# UI_MAIN.net
KiCad netlist of a schematic drawn in Altium Designer
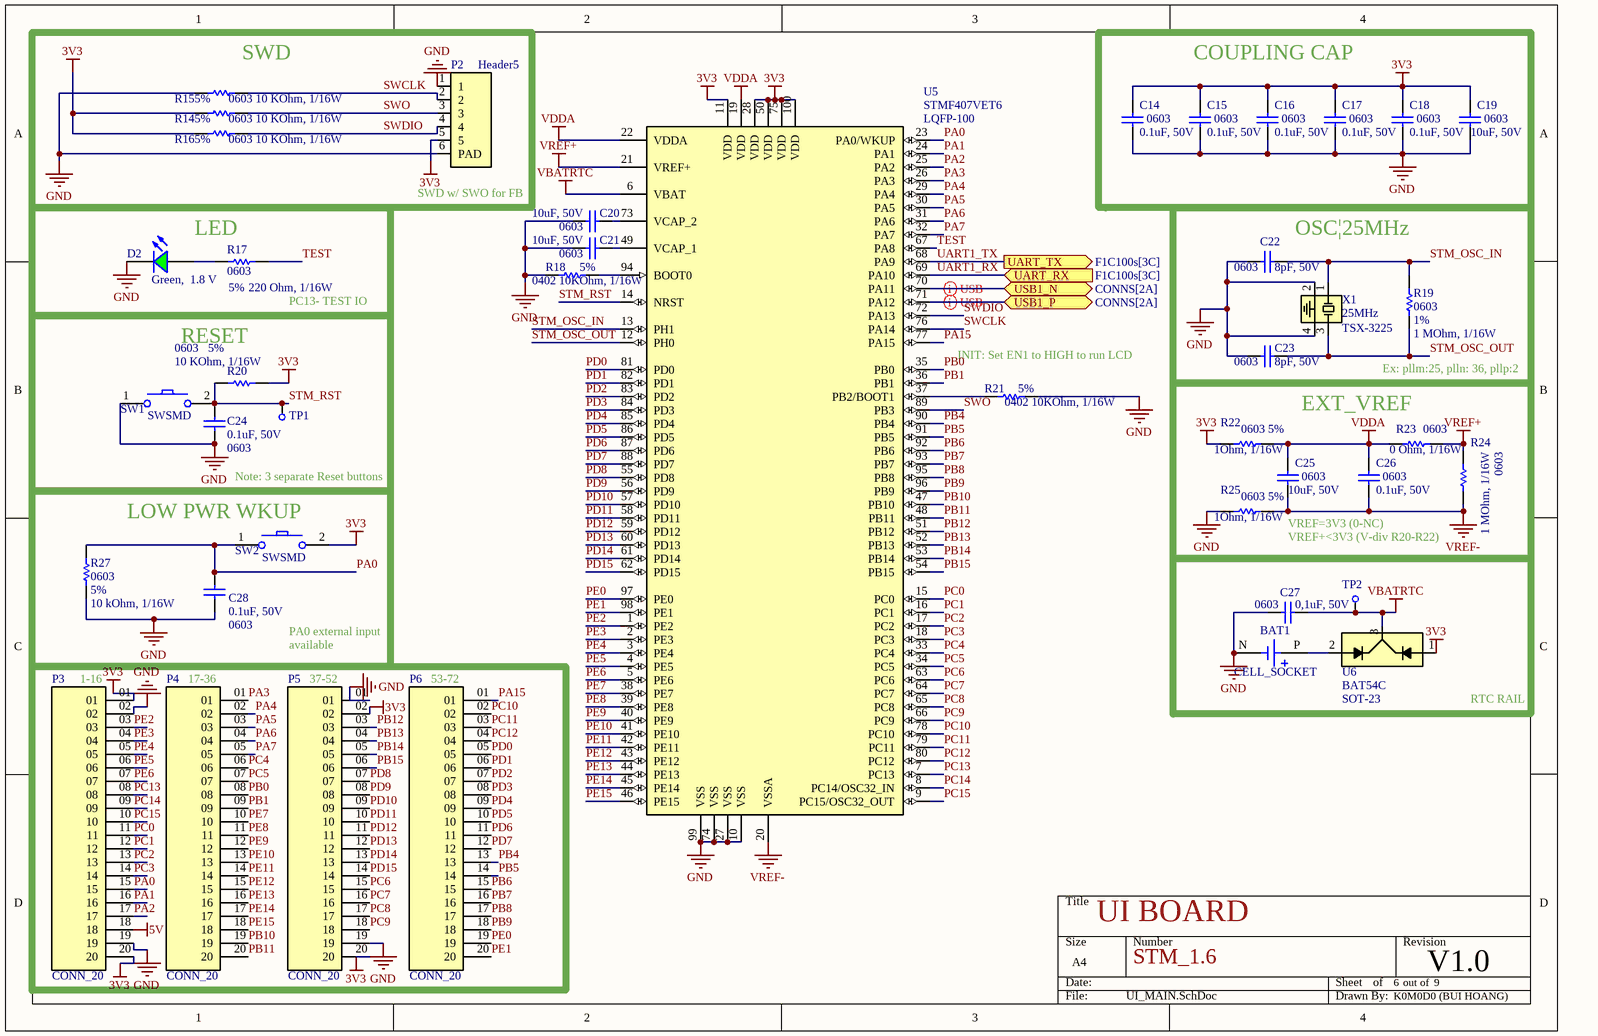
[diagram p0: UI_MAIN.SchDoc]

(export (version "E")
  (design (tool "Eeschema 10.0.6"))
  (components
    (comp (ref "BAT1")
      (value "CELL_SOCKET")
      (footprint "CELL_SOCKET")
      (description "Battery Holder (CELL_PIN)")
      (libsource (lib "DisplayLib") (part "CELL_SOCKET"))
    )
    (comp (ref "C14")
      (value "0.1uF, 50V")
      (footprint "C_0603")
      (description "CAP_0603")
      (fields (field (name "PACKAGE") "0603"))
      (libsource (lib "DisplayLib") (part "CAP_0603"))
    )
    (comp (ref "C15")
      (value "0.1uF, 50V")
      (footprint "C_0603")
      (description "CAP_0603")
      (fields (field (name "PACKAGE") "0603"))
      (libsource (lib "DisplayLib") (part "CAP_0603"))
    )
    (comp (ref "C16")
      (value "0.1uF, 50V")
      (footprint "C_0603")
      (description "CAP_0603")
      (fields (field (name "PACKAGE") "0603"))
      (libsource (lib "DisplayLib") (part "CAP_0603"))
    )
    (comp (ref "C17")
      (value "0.1uF, 50V")
      (footprint "C_0603")
      (description "CAP_0603")
      (fields (field (name "PACKAGE") "0603"))
      (libsource (lib "DisplayLib") (part "CAP_0603"))
    )
    (comp (ref "C18")
      (value "0.1uF, 50V")
      (footprint "C_0603")
      (description "CAP_0603")
      (fields (field (name "PACKAGE") "0603"))
      (libsource (lib "DisplayLib") (part "CAP_0603"))
    )
    (comp (ref "C19")
      (value "10uF, 50V")
      (footprint "C_0603")
      (description "CAP_0603")
      (fields (field (name "PACKAGE") "0603"))
      (libsource (lib "DisplayLib") (part "CAP_0603"))
    )
    (comp (ref "C20")
      (value "10uF, 50V")
      (footprint "C_0603")
      (description "CAP_0603")
      (fields (field (name "PACKAGE") "0603"))
      (libsource (lib "DisplayLib") (part "CAP_0603"))
    )
    (comp (ref "C21")
      (value "10uF, 50V")
      (footprint "C_0603")
      (description "CAP_0603")
      (fields (field (name "PACKAGE") "0603"))
      (libsource (lib "DisplayLib") (part "CAP_0603"))
    )
    (comp (ref "C22")
      (value "8pF, 50V")
      (footprint "C_0603")
      (description "CAP_0603")
      (fields (field (name "PACKAGE") "0603"))
      (libsource (lib "DisplayLib") (part "CAP_0603"))
    )
    (comp (ref "C23")
      (value "8pF, 50V")
      (footprint "C_0603")
      (description "CAP_0603")
      (fields (field (name "PACKAGE") "0603"))
      (libsource (lib "DisplayLib") (part "CAP_0603"))
    )
    (comp (ref "C24")
      (value "0.1uF, 50V")
      (footprint "C_0603")
      (description "CAP_0603")
      (fields (field (name "PACKAGE") "0603"))
      (libsource (lib "DisplayLib") (part "CAP_0603"))
    )
    (comp (ref "C25")
      (value "10uF, 50V")
      (footprint "C_0603")
      (description "CAP_0603")
      (fields (field (name "PACKAGE") "0603"))
      (libsource (lib "DisplayLib") (part "CAP_0603"))
    )
    (comp (ref "C26")
      (value "0.1uF, 50V")
      (footprint "C_0603")
      (description "CAP_0603")
      (fields (field (name "PACKAGE") "0603"))
      (libsource (lib "DisplayLib") (part "CAP_0603"))
    )
    (comp (ref "C27")
      (value "0,1uF, 50V")
      (footprint "C_0603")
      (description "CAP_0603")
      (fields (field (name "PACKAGE") "0603"))
      (libsource (lib "DisplayLib") (part "CAP_0603"))
    )
    (comp (ref "C28")
      (value "0.1uF, 50V")
      (footprint "C_0603")
      (description "CAP_0603")
      (fields (field (name "PACKAGE") "0603"))
      (libsource (lib "DisplayLib") (part "CAP_0603"))
    )
    (comp (ref "D2")
      (value "Green,  1.8 V")
      (footprint "LED_0603")
      (description "Green LED")
      (libsource (lib "DisplayLib") (part "GREEN"))
    )
    (comp (ref "P2")
      (value "Header5")
      (footprint "CONN_Header5")
      (description "Header 5 pins (2.54mm)")
      (libsource (lib "DisplayLib") (part "HEADER5"))
    )
    (comp (ref "P3")
      (value "CONN_20")
      (footprint "CONN_20")
      (description "Header 20 pins (2.54mm)")
      (libsource (lib "DisplayLib") (part "CONN_20"))
    )
    (comp (ref "P4")
      (value "CONN_20")
      (footprint "CONN_20")
      (description "Header 20 pins (2.54mm)")
      (libsource (lib "DisplayLib") (part "CONN_20"))
    )
    (comp (ref "P5")
      (value "CONN_20")
      (footprint "CONN_20")
      (description "Header 20 pins (2.54mm)")
      (libsource (lib "DisplayLib") (part "CONN_20"))
    )
    (comp (ref "P6")
      (value "CONN_20")
      (footprint "CONN_20")
      (description "Header 20 pins (2.54mm)")
      (libsource (lib "DisplayLib") (part "CONN_20"))
    )
    (comp (ref "R14")
      (value "10 KOhm, 1/16W")
      (footprint "R_0603")
      (description "RES_0603")
      (fields (field (name "PACKAGE") "0603") (field (name "ACC") "5%"))
      (libsource (lib "DisplayLib") (part "RES_0603"))
    )
    (comp (ref "R15")
      (value "10 KOhm, 1/16W")
      (footprint "R_0603")
      (description "RES_0603")
      (fields (field (name "PACKAGE") "0603") (field (name "ACC") "5%"))
      (libsource (lib "DisplayLib") (part "RES_0603"))
    )
    (comp (ref "R16")
      (value "10 KOhm, 1/16W")
      (footprint "R_0603")
      (description "RES_0603")
      (fields (field (name "PACKAGE") "0603") (field (name "ACC") "5%"))
      (libsource (lib "DisplayLib") (part "RES_0603"))
    )
    (comp (ref "R17")
      (value "220 Ohm, 1/16W")
      (footprint "R_0603")
      (description "RES_0603")
      (fields (field (name "PACKAGE") "0603") (field (name "ACC") "5%"))
      (libsource (lib "DisplayLib") (part "RES_0603"))
    )
    (comp (ref "R18")
      (value "10KOhm, 1/16W")
      (footprint "R_0402")
      (description "RES_0402")
      (fields (field (name "PACKAGE") "0402") (field (name "ACC") "5%"))
      (libsource (lib "DisplayLib") (part "RES_0402"))
    )
    (comp (ref "R19")
      (value "1 MOhm, 1/16W")
      (footprint "R_0603")
      (description "RES_0603")
      (fields (field (name "PACKAGE") "0603") (field (name "ACC") "1%"))
      (libsource (lib "DisplayLib") (part "RES_0603"))
    )
    (comp (ref "R20")
      (value "10 KOhm, 1/16W")
      (footprint "R_0603")
      (description "RES_0603")
      (fields (field (name "PACKAGE") "0603") (field (name "ACC") "5%"))
      (libsource (lib "DisplayLib") (part "RES_0603"))
    )
    (comp (ref "R21")
      (value "10KOhm, 1/16W")
      (footprint "R_0402")
      (description "RES_0402")
      (fields (field (name "PACKAGE") "0402") (field (name "ACC") "5%"))
      (libsource (lib "DisplayLib") (part "RES_0402"))
    )
    (comp (ref "R22")
      (value "1Ohm, 1/16W")
      (footprint "R_0603")
      (description "RES_0603")
      (fields (field (name "PACKAGE") "0603") (field (name "ACC") "5%"))
      (libsource (lib "DisplayLib") (part "RES_0603"))
    )
    (comp (ref "R23")
      (value "0 Ohm, 1/16W")
      (footprint "R_0603")
      (description "RES_0603")
      (fields (field (name "PACKAGE") "0603"))
      (libsource (lib "DisplayLib") (part "RES_0603"))
    )
    (comp (ref "R24")
      (value "1 MOhm, 1/16W")
      (footprint "R_0603")
      (description "RES_0603")
      (fields (field (name "PACKAGE") "0603"))
      (libsource (lib "DisplayLib") (part "RES_0603"))
    )
    (comp (ref "R25")
      (value "1Ohm, 1/16W")
      (footprint "R_0603")
      (description "RES_0603")
      (fields (field (name "PACKAGE") "0603") (field (name "ACC") "5%"))
      (libsource (lib "DisplayLib") (part "RES_0603"))
    )
    (comp (ref "R27")
      (value "10 kOhm, 1/16W")
      (footprint "R_0603")
      (description "RES_0603")
      (fields (field (name "PACKAGE") "0603") (field (name "ACC") "5%"))
      (libsource (lib "DisplayLib") (part "RES_0603"))
    )
    (comp (ref "SW1")
      (value "SWSMD")
      (footprint "SW_SMD_NOGND")
      (description "SW_SMD")
      (libsource (lib "DisplayLib") (part "SWSMD_NOGND"))
    )
    (comp (ref "SW2")
      (value "SWSMD")
      (footprint "SW_SMD_NOGND")
      (description "SW_SMD")
      (libsource (lib "DisplayLib") (part "SWSMD_NOGND"))
    )
    (comp (ref "TP1")
      (value "TESTPT")
      (footprint "TESTPT")
      (description "Test point")
      (libsource (lib "DisplayLib") (part "TESTPT"))
    )
    (comp (ref "TP2")
      (value "TESTPT")
      (footprint "TESTPT")
      (description "Test point")
      (libsource (lib "DisplayLib") (part "TESTPT"))
    )
    (comp (ref "U5")
      (value "STMF407VET6")
      (footprint "PKG_LQFP-100")
      (fields (field (name "PACKAGE") "LQFP-100"))
      (libsource (lib "DisplayLib") (part "STMF407VET6"))
    )
    (comp (ref "U6")
      (value "BAT54C")
      (footprint "PKG_SOT-23")
      (description "P-Channel 30 V 4A (Ta) 1.4W (Ta) Surface Mount SOT-23-3")
      (fields (field (name "PACKAGE") "SOT-23"))
      (libsource (lib "DisplayLib") (part "BAT54C"))
    )
    (comp (ref "X1")
      (value "25MHz")
      (footprint "PKG_TSX-3225")
      (description "Crystal, 25 MHz, -30 to 85 degC, 3.2 x 2.5 x 0.9 mm SMD")
      (fields (field (name "PACKAGE") "TSX-3225"))
      (libsource (lib "DisplayLib") (part "XTAL"))
    )
  )
  (nets
    (net (code "1") (name "/PA0") (class "Default")
      (node (ref "C28") (pin "2") (pinfunction "2_2") (pintype "passive"))
      (node (ref "P3") (pin "15") (pinfunction "15_15") (pintype "passive"))
      (node (ref "R27") (pin "2") (pinfunction "2_2") (pintype "passive"))
      (node (ref "SW2") (pin "1") (pinfunction "1_1") (pintype "passive"))
      (node (ref "U5") (pin "23") (pinfunction "PA0/WKUP_23") (pintype "bidirectional"))
    )
    (net (code "2") (name "/PA1") (class "Default")
      (node (ref "P3") (pin "16") (pinfunction "16_16") (pintype "passive"))
      (node (ref "U5") (pin "24") (pinfunction "PA1_24") (pintype "bidirectional"))
    )
    (net (code "3") (name "/PA2") (class "Default")
      (node (ref "P3") (pin "17") (pinfunction "17_17") (pintype "passive"))
      (node (ref "U5") (pin "25") (pinfunction "PA2_25") (pintype "bidirectional"))
    )
    (net (code "4") (name "/PA3") (class "Default")
      (node (ref "P4") (pin "01") (pinfunction "01_01") (pintype "passive"))
      (node (ref "U5") (pin "26") (pinfunction "PA3_26") (pintype "bidirectional"))
    )
    (net (code "5") (name "/PA4") (class "Default")
      (node (ref "P4") (pin "02") (pinfunction "02_02") (pintype "passive"))
      (node (ref "U5") (pin "29") (pinfunction "PA4_29") (pintype "bidirectional"))
    )
    (net (code "6") (name "/PA5") (class "Default")
      (node (ref "P4") (pin "03") (pinfunction "03_03") (pintype "passive"))
      (node (ref "U5") (pin "30") (pinfunction "PA5_30") (pintype "bidirectional"))
    )
    (net (code "7") (name "/PA6") (class "Default")
      (node (ref "P4") (pin "04") (pinfunction "04_04") (pintype "passive"))
      (node (ref "U5") (pin "31") (pinfunction "PA6_31") (pintype "bidirectional"))
    )
    (net (code "8") (name "/PA7") (class "Default")
      (node (ref "P4") (pin "05") (pinfunction "05_05") (pintype "passive"))
      (node (ref "U5") (pin "32") (pinfunction "PA7_32") (pintype "bidirectional"))
    )
    (net (code "9") (name "/PA15") (class "Default")
      (node (ref "P6") (pin "01") (pinfunction "01_01") (pintype "passive"))
      (node (ref "U5") (pin "77") (pinfunction "PA15_77") (pintype "bidirectional"))
    )
    (net (code "10") (name "/PB0") (class "Default")
      (node (ref "P4") (pin "08") (pinfunction "08_08") (pintype "passive"))
      (node (ref "U5") (pin "35") (pinfunction "PB0_35") (pintype "bidirectional"))
    )
    (net (code "11") (name "/PB1") (class "Default")
      (node (ref "P4") (pin "09") (pinfunction "09_09") (pintype "passive"))
      (node (ref "U5") (pin "36") (pinfunction "PB1_36") (pintype "bidirectional"))
    )
    (net (code "12") (name "/PB4") (class "Default")
      (node (ref "P6") (pin "13") (pinfunction "13_13") (pintype "passive"))
      (node (ref "U5") (pin "90") (pinfunction "PB4_90") (pintype "bidirectional"))
    )
    (net (code "13") (name "/PB5") (class "Default")
      (node (ref "P6") (pin "14") (pinfunction "14_14") (pintype "passive"))
      (node (ref "U5") (pin "91") (pinfunction "PB5_91") (pintype "bidirectional"))
    )
    (net (code "14") (name "/PB6") (class "Default")
      (node (ref "P6") (pin "15") (pinfunction "15_15") (pintype "passive"))
      (node (ref "U5") (pin "92") (pinfunction "PB6_92") (pintype "bidirectional"))
    )
    (net (code "15") (name "/PB7") (class "Default")
      (node (ref "P6") (pin "16") (pinfunction "16_16") (pintype "passive"))
      (node (ref "U5") (pin "93") (pinfunction "PB7_93") (pintype "bidirectional"))
    )
    (net (code "16") (name "/PB8") (class "Default")
      (node (ref "P6") (pin "17") (pinfunction "17_17") (pintype "passive"))
      (node (ref "U5") (pin "95") (pinfunction "PB8_95") (pintype "bidirectional"))
    )
    (net (code "17") (name "/PB9") (class "Default")
      (node (ref "P6") (pin "18") (pinfunction "18_18") (pintype "passive"))
      (node (ref "U5") (pin "96") (pinfunction "PB9_96") (pintype "bidirectional"))
    )
    (net (code "18") (name "/PB10") (class "Default")
      (node (ref "P4") (pin "19") (pinfunction "19_19") (pintype "passive"))
      (node (ref "U5") (pin "47") (pinfunction "PB10_47") (pintype "bidirectional"))
    )
    (net (code "19") (name "/PB11") (class "Default")
      (node (ref "P4") (pin "20") (pinfunction "20_20") (pintype "passive"))
      (node (ref "U5") (pin "48") (pinfunction "PB11_48") (pintype "bidirectional"))
    )
    (net (code "20") (name "/PB12") (class "Default")
      (node (ref "P5") (pin "03") (pinfunction "03_03") (pintype "passive"))
      (node (ref "U5") (pin "51") (pinfunction "PB12_51") (pintype "bidirectional"))
    )
    (net (code "21") (name "/PB13") (class "Default")
      (node (ref "P5") (pin "04") (pinfunction "04_04") (pintype "passive"))
      (node (ref "U5") (pin "52") (pinfunction "PB13_52") (pintype "bidirectional"))
    )
    (net (code "22") (name "/PB14") (class "Default")
      (node (ref "P5") (pin "05") (pinfunction "05_05") (pintype "passive"))
      (node (ref "U5") (pin "53") (pinfunction "PB14_53") (pintype "bidirectional"))
    )
    (net (code "23") (name "/PB15") (class "Default")
      (node (ref "P5") (pin "06") (pinfunction "06_06") (pintype "passive"))
      (node (ref "U5") (pin "54") (pinfunction "PB15_54") (pintype "bidirectional"))
    )
    (net (code "24") (name "/PC0") (class "Default")
      (node (ref "P3") (pin "11") (pinfunction "11_11") (pintype "passive"))
      (node (ref "U5") (pin "15") (pinfunction "PC0_15") (pintype "bidirectional"))
    )
    (net (code "25") (name "/PC1") (class "Default")
      (node (ref "P3") (pin "12") (pinfunction "12_12") (pintype "passive"))
      (node (ref "U5") (pin "16") (pinfunction "PC1_16") (pintype "bidirectional"))
    )
    (net (code "26") (name "/PC2") (class "Default")
      (node (ref "P3") (pin "13") (pinfunction "13_13") (pintype "passive"))
      (node (ref "U5") (pin "17") (pinfunction "PC2_17") (pintype "bidirectional"))
    )
    (net (code "27") (name "/PC3") (class "Default")
      (node (ref "P3") (pin "14") (pinfunction "14_14") (pintype "passive"))
      (node (ref "U5") (pin "18") (pinfunction "PC3_18") (pintype "bidirectional"))
    )
    (net (code "28") (name "/PC4") (class "Default")
      (node (ref "P4") (pin "06") (pinfunction "06_06") (pintype "passive"))
      (node (ref "U5") (pin "33") (pinfunction "PC4_33") (pintype "bidirectional"))
    )
    (net (code "29") (name "/PC5") (class "Default")
      (node (ref "P4") (pin "07") (pinfunction "07_07") (pintype "passive"))
      (node (ref "U5") (pin "34") (pinfunction "PC5_34") (pintype "bidirectional"))
    )
    (net (code "30") (name "/PC6") (class "Default")
      (node (ref "P5") (pin "15") (pinfunction "15_15") (pintype "passive"))
      (node (ref "U5") (pin "63") (pinfunction "PC6_63") (pintype "bidirectional"))
    )
    (net (code "31") (name "/PC7") (class "Default")
      (node (ref "P5") (pin "16") (pinfunction "16_16") (pintype "passive"))
      (node (ref "U5") (pin "64") (pinfunction "PC7_64") (pintype "bidirectional"))
    )
    (net (code "32") (name "/PC8") (class "Default")
      (node (ref "P5") (pin "17") (pinfunction "17_17") (pintype "passive"))
      (node (ref "U5") (pin "65") (pinfunction "PC8_65") (pintype "bidirectional"))
    )
    (net (code "33") (name "/PC9") (class "Default")
      (node (ref "P5") (pin "18") (pinfunction "18_18") (pintype "passive"))
      (node (ref "U5") (pin "66") (pinfunction "PC9_66") (pintype "bidirectional"))
    )
    (net (code "34") (name "/PC10") (class "Default")
      (node (ref "P6") (pin "02") (pinfunction "02_02") (pintype "passive"))
      (node (ref "U5") (pin "78") (pinfunction "PC10_78") (pintype "bidirectional"))
    )
    (net (code "35") (name "/PC11") (class "Default")
      (node (ref "P6") (pin "03") (pinfunction "03_03") (pintype "passive"))
      (node (ref "U5") (pin "79") (pinfunction "PC11_79") (pintype "bidirectional"))
    )
    (net (code "36") (name "/PC12") (class "Default")
      (node (ref "P6") (pin "04") (pinfunction "04_04") (pintype "passive"))
      (node (ref "U5") (pin "80") (pinfunction "PC12_80") (pintype "bidirectional"))
    )
    (net (code "37") (name "/PC13") (class "Default")
      (node (ref "P3") (pin "08") (pinfunction "08_08") (pintype "passive"))
      (node (ref "U5") (pin "7") (pinfunction "PC13_7") (pintype "bidirectional"))
    )
    (net (code "38") (name "/PC14") (class "Default")
      (node (ref "P3") (pin "09") (pinfunction "09_09") (pintype "passive"))
      (node (ref "U5") (pin "8") (pinfunction "PC14/OSC32_IN_8") (pintype "bidirectional"))
    )
    (net (code "39") (name "/PC15") (class "Default")
      (node (ref "P3") (pin "10") (pinfunction "10_10") (pintype "passive"))
      (node (ref "U5") (pin "9") (pinfunction "PC15/OSC32_OUT_9") (pintype "bidirectional"))
    )
    (net (code "40") (name "/PD0") (class "Default")
      (node (ref "P6") (pin "05") (pinfunction "05_05") (pintype "passive"))
      (node (ref "U5") (pin "81") (pinfunction "PD0_81") (pintype "bidirectional"))
    )
    (net (code "41") (name "/PD1") (class "Default")
      (node (ref "P6") (pin "06") (pinfunction "06_06") (pintype "passive"))
      (node (ref "U5") (pin "82") (pinfunction "PD1_82") (pintype "bidirectional"))
    )
    (net (code "42") (name "/PD2") (class "Default")
      (node (ref "P6") (pin "07") (pinfunction "07_07") (pintype "passive"))
      (node (ref "U5") (pin "83") (pinfunction "PD2_83") (pintype "bidirectional"))
    )
    (net (code "43") (name "/PD3") (class "Default")
      (node (ref "P6") (pin "08") (pinfunction "08_08") (pintype "passive"))
      (node (ref "U5") (pin "84") (pinfunction "PD3_84") (pintype "bidirectional"))
    )
    (net (code "44") (name "/PD4") (class "Default")
      (node (ref "P6") (pin "09") (pinfunction "09_09") (pintype "passive"))
      (node (ref "U5") (pin "85") (pinfunction "PD4_85") (pintype "bidirectional"))
    )
    (net (code "45") (name "/PD5") (class "Default")
      (node (ref "P6") (pin "10") (pinfunction "10_10") (pintype "passive"))
      (node (ref "U5") (pin "86") (pinfunction "PD5_86") (pintype "bidirectional"))
    )
    (net (code "46") (name "/PD6") (class "Default")
      (node (ref "P6") (pin "11") (pinfunction "11_11") (pintype "passive"))
      (node (ref "U5") (pin "87") (pinfunction "PD6_87") (pintype "bidirectional"))
    )
    (net (code "47") (name "/PD7") (class "Default")
      (node (ref "P6") (pin "12") (pinfunction "12_12") (pintype "passive"))
      (node (ref "U5") (pin "88") (pinfunction "PD7_88") (pintype "bidirectional"))
    )
    (net (code "48") (name "/PD8") (class "Default")
      (node (ref "P5") (pin "07") (pinfunction "07_07") (pintype "passive"))
      (node (ref "U5") (pin "55") (pinfunction "PD8_55") (pintype "bidirectional"))
    )
    (net (code "49") (name "/PD9") (class "Default")
      (node (ref "P5") (pin "08") (pinfunction "08_08") (pintype "passive"))
      (node (ref "U5") (pin "56") (pinfunction "PD9_56") (pintype "bidirectional"))
    )
    (net (code "50") (name "/PD10") (class "Default")
      (node (ref "P5") (pin "09") (pinfunction "09_09") (pintype "passive"))
      (node (ref "U5") (pin "57") (pinfunction "PD10_57") (pintype "bidirectional"))
    )
    (net (code "51") (name "/PD11") (class "Default")
      (node (ref "P5") (pin "10") (pinfunction "10_10") (pintype "passive"))
      (node (ref "U5") (pin "58") (pinfunction "PD11_58") (pintype "bidirectional"))
    )
    (net (code "52") (name "/PD12") (class "Default")
      (node (ref "P5") (pin "11") (pinfunction "11_11") (pintype "passive"))
      (node (ref "U5") (pin "59") (pinfunction "PD12_59") (pintype "bidirectional"))
    )
    (net (code "53") (name "/PD13") (class "Default")
      (node (ref "P5") (pin "12") (pinfunction "12_12") (pintype "passive"))
      (node (ref "U5") (pin "60") (pinfunction "PD13_60") (pintype "bidirectional"))
    )
    (net (code "54") (name "/PD14") (class "Default")
      (node (ref "P5") (pin "13") (pinfunction "13_13") (pintype "passive"))
      (node (ref "U5") (pin "61") (pinfunction "PD14_61") (pintype "bidirectional"))
    )
    (net (code "55") (name "/PD15") (class "Default")
      (node (ref "P5") (pin "14") (pinfunction "14_14") (pintype "passive"))
      (node (ref "U5") (pin "62") (pinfunction "PD15_62") (pintype "bidirectional"))
    )
    (net (code "56") (name "/PE0") (class "Default")
      (node (ref "P6") (pin "19") (pinfunction "19_19") (pintype "passive"))
      (node (ref "U5") (pin "97") (pinfunction "PE0_97") (pintype "bidirectional"))
    )
    (net (code "57") (name "/PE1") (class "Default")
      (node (ref "P6") (pin "20") (pinfunction "20_20") (pintype "passive"))
      (node (ref "U5") (pin "98") (pinfunction "PE1_98") (pintype "bidirectional"))
    )
    (net (code "58") (name "/PE2") (class "Default")
      (node (ref "P3") (pin "03") (pinfunction "03_03") (pintype "passive"))
      (node (ref "U5") (pin "1") (pinfunction "PE2_1") (pintype "bidirectional"))
    )
    (net (code "59") (name "/PE3") (class "Default")
      (node (ref "P3") (pin "04") (pinfunction "04_04") (pintype "passive"))
      (node (ref "U5") (pin "2") (pinfunction "PE3_2") (pintype "bidirectional"))
    )
    (net (code "60") (name "/PE4") (class "Default")
      (node (ref "P3") (pin "05") (pinfunction "05_05") (pintype "passive"))
      (node (ref "U5") (pin "3") (pinfunction "PE4_3") (pintype "bidirectional"))
    )
    (net (code "61") (name "/PE5") (class "Default")
      (node (ref "P3") (pin "06") (pinfunction "06_06") (pintype "passive"))
      (node (ref "U5") (pin "4") (pinfunction "PE5_4") (pintype "bidirectional"))
    )
    (net (code "62") (name "/PE6") (class "Default")
      (node (ref "P3") (pin "07") (pinfunction "07_07") (pintype "passive"))
      (node (ref "U5") (pin "5") (pinfunction "PE6_5") (pintype "bidirectional"))
    )
    (net (code "63") (name "/PE7") (class "Default")
      (node (ref "P4") (pin "10") (pinfunction "10_10") (pintype "passive"))
      (node (ref "U5") (pin "38") (pinfunction "PE7_38") (pintype "bidirectional"))
    )
    (net (code "64") (name "/PE8") (class "Default")
      (node (ref "P4") (pin "11") (pinfunction "11_11") (pintype "passive"))
      (node (ref "U5") (pin "39") (pinfunction "PE8_39") (pintype "bidirectional"))
    )
    (net (code "65") (name "/PE9") (class "Default")
      (node (ref "P4") (pin "12") (pinfunction "12_12") (pintype "passive"))
      (node (ref "U5") (pin "40") (pinfunction "PE9_40") (pintype "bidirectional"))
    )
    (net (code "66") (name "/PE10") (class "Default")
      (node (ref "P4") (pin "13") (pinfunction "13_13") (pintype "passive"))
      (node (ref "U5") (pin "41") (pinfunction "PE10_41") (pintype "bidirectional"))
    )
    (net (code "67") (name "/PE11") (class "Default")
      (node (ref "P4") (pin "14") (pinfunction "14_14") (pintype "passive"))
      (node (ref "U5") (pin "42") (pinfunction "PE11_42") (pintype "bidirectional"))
    )
    (net (code "68") (name "/PE12") (class "Default")
      (node (ref "P4") (pin "15") (pinfunction "15_15") (pintype "passive"))
      (node (ref "U5") (pin "43") (pinfunction "PE12_43") (pintype "bidirectional"))
    )
    (net (code "69") (name "/PE13") (class "Default")
      (node (ref "P4") (pin "16") (pinfunction "16_16") (pintype "passive"))
      (node (ref "U5") (pin "44") (pinfunction "PE13_44") (pintype "bidirectional"))
    )
    (net (code "70") (name "/PE14") (class "Default")
      (node (ref "P4") (pin "17") (pinfunction "17_17") (pintype "passive"))
      (node (ref "U5") (pin "45") (pinfunction "PE14_45") (pintype "bidirectional"))
    )
    (net (code "71") (name "/PE15") (class "Default")
      (node (ref "P4") (pin "18") (pinfunction "18_18") (pintype "passive"))
      (node (ref "U5") (pin "46") (pinfunction "PE15_46") (pintype "bidirectional"))
    )
    (net (code "72") (name "/STM_OSC_IN") (class "Default")
      (node (ref "C22") (pin "2") (pinfunction "2_2") (pintype "passive"))
      (node (ref "R19") (pin "2") (pinfunction "2_2") (pintype "passive"))
      (node (ref "U5") (pin "13") (pinfunction "PH1_13") (pintype "bidirectional"))
      (node (ref "X1") (pin "1") (pinfunction "1_1") (pintype "passive"))
    )
    (net (code "73") (name "/STM_OSC_OUT") (class "Default")
      (node (ref "C23") (pin "2") (pinfunction "2_2") (pintype "passive"))
      (node (ref "R19") (pin "1") (pinfunction "1_1") (pintype "passive"))
      (node (ref "U5") (pin "12") (pinfunction "PH0_12") (pintype "bidirectional"))
      (node (ref "X1") (pin "3") (pinfunction "3_3") (pintype "passive"))
    )
    (net (code "74") (name "/STM_RST") (class "Default")
      (node (ref "C24") (pin "2") (pinfunction "2_2") (pintype "passive"))
      (node (ref "R20") (pin "1") (pinfunction "1_1") (pintype "passive"))
      (node (ref "SW1") (pin "2") (pinfunction "2_2") (pintype "passive"))
      (node (ref "TP1") (pin "1") (pinfunction "1_1") (pintype "passive"))
      (node (ref "U5") (pin "14") (pinfunction "NRST_14") (pintype "bidirectional"))
    )
    (net (code "75") (name "/SWCLK") (class "Default")
      (node (ref "P2") (pin "2") (pinfunction "2_2") (pintype "passive"))
      (node (ref "R15") (pin "2") (pinfunction "2_2") (pintype "passive"))
      (node (ref "U5") (pin "76") (pinfunction "PA14_76") (pintype "bidirectional"))
    )
    (net (code "76") (name "/SWDIO") (class "Default")
      (node (ref "P2") (pin "4") (pinfunction "4_4") (pintype "passive"))
      (node (ref "R16") (pin "2") (pinfunction "2_2") (pintype "passive"))
      (node (ref "U5") (pin "72") (pinfunction "PA13_72") (pintype "bidirectional"))
    )
    (net (code "77") (name "/SWO") (class "Default")
      (node (ref "P2") (pin "3") (pinfunction "3_3") (pintype "passive"))
      (node (ref "R14") (pin "2") (pinfunction "2_2") (pintype "passive"))
      (node (ref "U5") (pin "89") (pinfunction "PB3_89") (pintype "bidirectional"))
    )
    (net (code "78") (name "/TEST") (class "Default")
      (node (ref "R17") (pin "2") (pinfunction "2_2") (pintype "passive"))
      (node (ref "U5") (pin "67") (pinfunction "PA8_67") (pintype "bidirectional"))
    )
    (net (code "79") (name "/UART1_RX") (class "Default")
      (node (ref "U5") (pin "69") (pinfunction "PA10_69") (pintype "bidirectional"))
    )
    (net (code "80") (name "/UART1_TX") (class "Default")
      (node (ref "U5") (pin "68") (pinfunction "PA9_68") (pintype "bidirectional"))
    )
    (net (code "81") (name "/USB1_N") (class "Default")
      (node (ref "U5") (pin "70") (pinfunction "PA11_70") (pintype "bidirectional"))
    )
    (net (code "82") (name "/USB1_P") (class "Default")
      (node (ref "U5") (pin "71") (pinfunction "PA12_71") (pintype "bidirectional"))
    )
    (net (code "83") (name "3V3") (class "Default")
      (node (ref "C14") (pin "2") (pinfunction "2_2") (pintype "passive"))
      (node (ref "C15") (pin "2") (pinfunction "2_2") (pintype "passive"))
      (node (ref "C16") (pin "2") (pinfunction "2_2") (pintype "passive"))
      (node (ref "C17") (pin "2") (pinfunction "2_2") (pintype "passive"))
      (node (ref "C18") (pin "2") (pinfunction "2_2") (pintype "passive"))
      (node (ref "C19") (pin "2") (pinfunction "2_2") (pintype "passive"))
      (node (ref "P2") (pin "5") (pinfunction "5_5") (pintype "passive"))
      (node (ref "P3") (pin "01") (pinfunction "01_01") (pintype "passive"))
      (node (ref "P3") (pin "20") (pinfunction "20_20") (pintype "passive"))
      (node (ref "P5") (pin "02") (pinfunction "02_02") (pintype "passive"))
      (node (ref "P5") (pin "20") (pinfunction "20_20") (pintype "passive"))
      (node (ref "R14") (pin "1") (pinfunction "1_1") (pintype "passive"))
      (node (ref "R16") (pin "1") (pinfunction "1_1") (pintype "passive"))
      (node (ref "R20") (pin "2") (pinfunction "2_2") (pintype "passive"))
      (node (ref "R22") (pin "1") (pinfunction "1_1") (pintype "passive"))
      (node (ref "SW2") (pin "2") (pinfunction "2_2") (pintype "passive"))
      (node (ref "U5") (pin "100") (pinfunction "VDD_100") (pintype "power_in"))
      (node (ref "U5") (pin "11") (pinfunction "VDD_11") (pintype "power_in"))
      (node (ref "U5") (pin "28") (pinfunction "VDD_28") (pintype "power_in"))
      (node (ref "U5") (pin "50") (pinfunction "VDD_50") (pintype "power_in"))
      (node (ref "U5") (pin "75") (pinfunction "VDD_75") (pintype "power_in"))
      (node (ref "U6") (pin "1") (pinfunction "1_1") (pintype "power_in"))
    )
    (net (code "84") (name "5V") (class "Default")
      (node (ref "P3") (pin "18") (pinfunction "18_18") (pintype "passive"))
    )
    (net (code "85") (name "GND") (class "Default")
      (node (ref "BAT1") (pin "N") (pinfunction "N_N") (pintype "passive"))
      (node (ref "C14") (pin "1") (pinfunction "1_1") (pintype "passive"))
      (node (ref "C15") (pin "1") (pinfunction "1_1") (pintype "passive"))
      (node (ref "C16") (pin "1") (pinfunction "1_1") (pintype "passive"))
      (node (ref "C17") (pin "1") (pinfunction "1_1") (pintype "passive"))
      (node (ref "C18") (pin "1") (pinfunction "1_1") (pintype "passive"))
      (node (ref "C19") (pin "1") (pinfunction "1_1") (pintype "passive"))
      (node (ref "C20") (pin "2") (pinfunction "2_2") (pintype "passive"))
      (node (ref "C21") (pin "2") (pinfunction "2_2") (pintype "passive"))
      (node (ref "C22") (pin "1") (pinfunction "1_1") (pintype "passive"))
      (node (ref "C23") (pin "1") (pinfunction "1_1") (pintype "passive"))
      (node (ref "C24") (pin "1") (pinfunction "1_1") (pintype "passive"))
      (node (ref "C27") (pin "1") (pinfunction "1_1") (pintype "passive"))
      (node (ref "C28") (pin "1") (pinfunction "1_1") (pintype "passive"))
      (node (ref "D2") (pin "1") (pinfunction "K_1") (pintype "passive"))
      (node (ref "P2") (pin "1") (pinfunction "1_1") (pintype "passive"))
      (node (ref "P2") (pin "6") (pinfunction "PAD_6") (pintype "passive"))
      (node (ref "P3") (pin "02") (pinfunction "02_02") (pintype "passive"))
      (node (ref "P3") (pin "19") (pinfunction "19_19") (pintype "passive"))
      (node (ref "P5") (pin "01") (pinfunction "01_01") (pintype "passive"))
      (node (ref "P5") (pin "19") (pinfunction "19_19") (pintype "passive"))
      (node (ref "R15") (pin "1") (pinfunction "1_1") (pintype "passive"))
      (node (ref "R18") (pin "1") (pinfunction "1_1") (pintype "passive"))
      (node (ref "R21") (pin "2") (pinfunction "2_2") (pintype "passive"))
      (node (ref "R25") (pin "1") (pinfunction "1_1") (pintype "passive"))
      (node (ref "R27") (pin "1") (pinfunction "1_1") (pintype "passive"))
      (node (ref "SW1") (pin "1") (pinfunction "1_1") (pintype "passive"))
      (node (ref "U5") (pin "10") (pinfunction "VSS_10") (pintype "power_in"))
      (node (ref "U5") (pin "27") (pinfunction "VSS_27") (pintype "power_in"))
      (node (ref "U5") (pin "74") (pinfunction "VSS_74") (pintype "power_in"))
      (node (ref "U5") (pin "99") (pinfunction "VSS_99") (pintype "power_in"))
      (node (ref "X1") (pin "2") (pinfunction "2_2") (pintype "passive"))
      (node (ref "X1") (pin "4") (pinfunction "4_4") (pintype "passive"))
    )
    (net (code "86") (name "Net-(BAT1-PadP)") (class "Default")
      (node (ref "BAT1") (pin "P") (pinfunction "P_P") (pintype "passive"))
      (node (ref "U6") (pin "2") (pinfunction "2_2") (pintype "passive"))
    )
    (net (code "87") (name "Net-(D2-A)") (class "Default")
      (node (ref "D2") (pin "2") (pinfunction "A_2") (pintype "passive"))
      (node (ref "R17") (pin "1") (pinfunction "1_1") (pintype "passive"))
    )
    (net (code "88") (name "Net-(U5-BOOT0)") (class "Default")
      (node (ref "R18") (pin "2") (pinfunction "2_2") (pintype "passive"))
      (node (ref "U5") (pin "94") (pinfunction "BOOT0_94") (pintype "input"))
    )
    (net (code "89") (name "Net-(U5-PB2{slash}BOOT1)") (class "Default")
      (node (ref "R21") (pin "1") (pinfunction "1_1") (pintype "passive"))
      (node (ref "U5") (pin "37") (pinfunction "PB2/BOOT1_37") (pintype "bidirectional"))
    )
    (net (code "90") (name "Net-(U5-VCAP_1)") (class "Default")
      (node (ref "C21") (pin "1") (pinfunction "1_1") (pintype "passive"))
      (node (ref "U5") (pin "49") (pinfunction "VCAP_1_49") (pintype "power_in"))
    )
    (net (code "91") (name "Net-(U5-VCAP_2)") (class "Default")
      (node (ref "C20") (pin "1") (pinfunction "1_1") (pintype "passive"))
      (node (ref "U5") (pin "73") (pinfunction "VCAP_2_73") (pintype "power_in"))
    )
    (net (code "92") (name "VBATRTC") (class "Default")
      (node (ref "C27") (pin "2") (pinfunction "2_2") (pintype "passive"))
      (node (ref "TP2") (pin "1") (pinfunction "1_1") (pintype "passive"))
      (node (ref "U5") (pin "6") (pinfunction "VBAT_6") (pintype "power_in"))
      (node (ref "U6") (pin "3") (pinfunction "3_3") (pintype "passive"))
    )
    (net (code "93") (name "VDDA") (class "Default")
      (node (ref "C25") (pin "2") (pinfunction "2_2") (pintype "passive"))
      (node (ref "C26") (pin "2") (pinfunction "2_2") (pintype "passive"))
      (node (ref "R22") (pin "2") (pinfunction "2_2") (pintype "passive"))
      (node (ref "R23") (pin "1") (pinfunction "1_1") (pintype "passive"))
      (node (ref "U5") (pin "19") (pinfunction "VDD_19") (pintype "power_in"))
      (node (ref "U5") (pin "22") (pinfunction "VDDA_22") (pintype "power_in"))
    )
    (net (code "94") (name "VREF+") (class "Default")
      (node (ref "R23") (pin "2") (pinfunction "2_2") (pintype "passive"))
      (node (ref "R24") (pin "2") (pinfunction "2_2") (pintype "passive"))
      (node (ref "U5") (pin "21") (pinfunction "VREF+_21") (pintype "power_in"))
    )
    (net (code "95") (name "VREF-") (class "Default")
      (node (ref "C25") (pin "1") (pinfunction "1_1") (pintype "passive"))
      (node (ref "C26") (pin "1") (pinfunction "1_1") (pintype "passive"))
      (node (ref "R24") (pin "1") (pinfunction "1_1") (pintype "passive"))
      (node (ref "R25") (pin "2") (pinfunction "2_2") (pintype "passive"))
      (node (ref "U5") (pin "20") (pinfunction "VSSA_20") (pintype "power_in"))
    )
  )
)
